# UAV_ARM.net
KiCad netlist of a schematic drawn in EAGLE
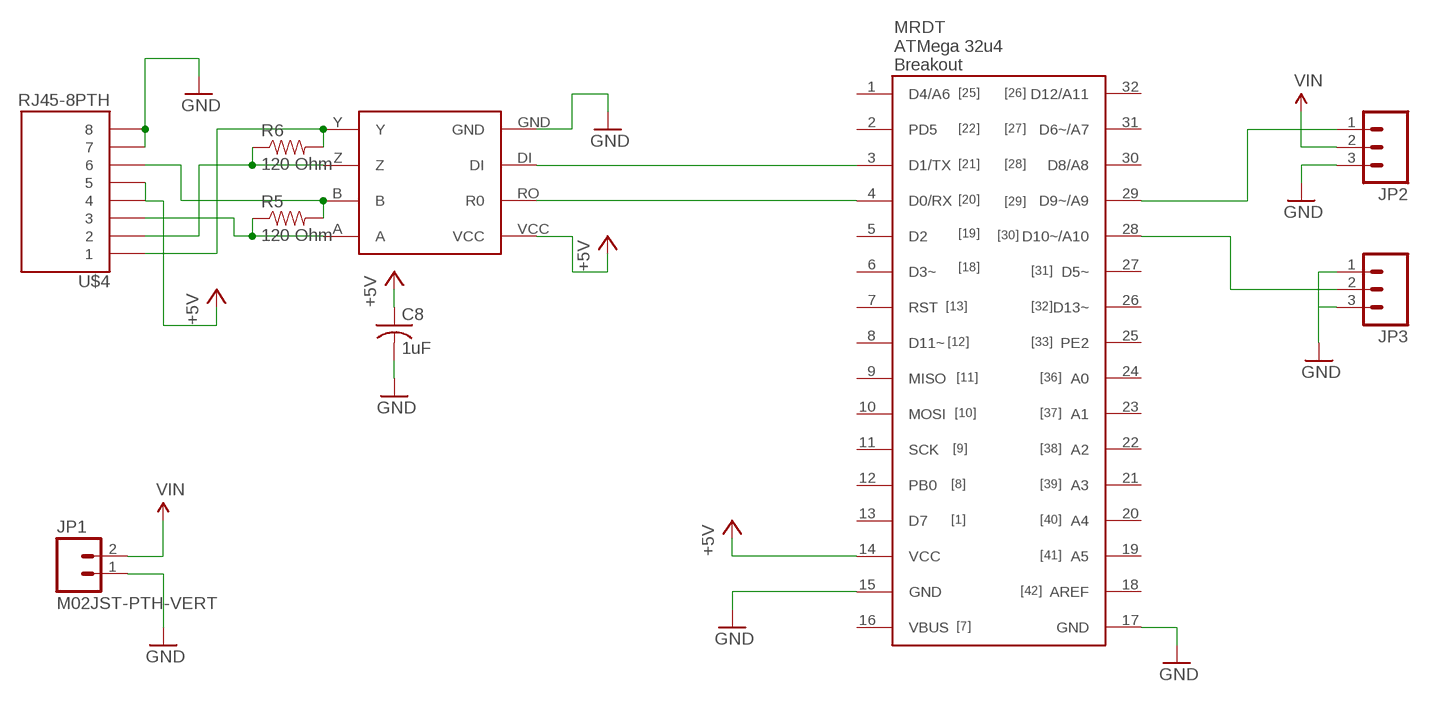
[diagram p0: schematic, sheet 1]

(export (version "E")
  (design (tool "Eeschema 10.0.6"))
  (components
    (comp (ref "C8")
      (value "1uF")
      (footprint "eagle-import:C1206")
      (libsource (lib "eagle-import") (part "C-USC1206"))
    )
    (comp (ref "JP1")
      (value "M02JST-PTH-VERT")
      (footprint "eagle-import:JST-2-PTH-VERT")
      (libsource (lib "eagle-import") (part "M02JST-PTH-VERT"))
    )
    (comp (ref "JP2")
      (value "M03JST-PTH")
      (footprint "eagle-import:JST-3-PTH")
      (libsource (lib "eagle-import") (part "M03JST-PTH"))
    )
    (comp (ref "JP3")
      (value "M03JST-PTH")
      (footprint "eagle-import:JST-3-PTH")
      (libsource (lib "eagle-import") (part "M03JST-PTH"))
    )
    (comp (ref "R5")
      (value "120 Ohm")
      (footprint "eagle-import:1206")
      (libsource (lib "eagle-import") (part "RESISTOR1206"))
    )
    (comp (ref "R6")
      (value "120 Ohm")
      (footprint "eagle-import:1206")
      (libsource (lib "eagle-import") (part "RESISTOR1206"))
    )
    (comp (ref "U$2")
      (value "32U4_BREAKOUT")
      (footprint "eagle-import:32U4_MCU_DIP")
      (libsource (lib "eagle-import") (part "32U4_BREAKOUT"))
    )
    (comp (ref "U$3")
      (value "MAX3077")
      (footprint "eagle-import:MAX3070E")
      (libsource (lib "eagle-import") (part "MAX3077"))
    )
    (comp (ref "U$4")
      (value "RJ45-8PTH")
      (footprint "eagle-import:RJ45-8")
      (libsource (lib "eagle-import") (part "RJ45-8PTH"))
    )
  )
  (nets
    (net (code "1") (name "+5V") (class "Default")
      (node (ref "C8") (pin "1") (pinfunction "1_1") (pintype "passive"))
      (node (ref "U$2") (pin "14") (pinfunction "VCC_14") (pintype "bidirectional"))
      (node (ref "U$3") (pin "VCC") (pinfunction "VCC_VCC") (pintype "bidirectional"))
      (node (ref "U$4") (pin "4") (pinfunction "4_4") (pintype "bidirectional"))
      (node (ref "U$4") (pin "5") (pinfunction "5_5") (pintype "bidirectional"))
    )
    (net (code "2") (name "GND") (class "Default")
      (node (ref "C8") (pin "2") (pinfunction "2_2") (pintype "passive"))
      (node (ref "JP1") (pin "1") (pinfunction "1_1") (pintype "passive"))
      (node (ref "JP2") (pin "3") (pinfunction "3_3") (pintype "passive"))
      (node (ref "JP3") (pin "1") (pinfunction "1_1") (pintype "passive"))
      (node (ref "JP3") (pin "3") (pinfunction "3_3") (pintype "passive"))
      (node (ref "U$2") (pin "15") (pinfunction "GND_15") (pintype "bidirectional"))
      (node (ref "U$2") (pin "17") (pinfunction "GND_17") (pintype "bidirectional"))
      (node (ref "U$3") (pin "GND") (pinfunction "GND_GND") (pintype "bidirectional"))
      (node (ref "U$4") (pin "7") (pinfunction "7_7") (pintype "bidirectional"))
      (node (ref "U$4") (pin "8") (pinfunction "8_8") (pintype "bidirectional"))
    )
    (net (code "3") (name "Net-(R5-Pad1)") (class "Default")
      (node (ref "R5") (pin "1") (pinfunction "1_1") (pintype "passive"))
      (node (ref "U$3") (pin "A") (pinfunction "A_A") (pintype "bidirectional"))
      (node (ref "U$4") (pin "3") (pinfunction "3_3") (pintype "bidirectional"))
    )
    (net (code "4") (name "Net-(R5-Pad2)") (class "Default")
      (node (ref "R5") (pin "2") (pinfunction "2_2") (pintype "passive"))
      (node (ref "U$3") (pin "B") (pinfunction "B_B") (pintype "bidirectional"))
      (node (ref "U$4") (pin "6") (pinfunction "6_6") (pintype "bidirectional"))
    )
    (net (code "5") (name "Net-(R6-Pad1)") (class "Default")
      (node (ref "R6") (pin "1") (pinfunction "1_1") (pintype "passive"))
      (node (ref "U$3") (pin "Z") (pinfunction "Z_Z") (pintype "bidirectional"))
      (node (ref "U$4") (pin "2") (pinfunction "2_2") (pintype "bidirectional"))
    )
    (net (code "6") (name "Net-(R6-Pad2)") (class "Default")
      (node (ref "R6") (pin "2") (pinfunction "2_2") (pintype "passive"))
      (node (ref "U$3") (pin "Y") (pinfunction "Y_Y") (pintype "bidirectional"))
      (node (ref "U$4") (pin "1") (pinfunction "1_1") (pintype "bidirectional"))
    )
    (net (code "7") (name "Net-(U$2-D0{slash}RX)") (class "Default")
      (node (ref "U$2") (pin "4") (pinfunction "D0/RX_4") (pintype "bidirectional"))
      (node (ref "U$3") (pin "RO") (pinfunction "R0_RO") (pintype "bidirectional"))
    )
    (net (code "8") (name "Net-(U$2-D1{slash}TX)") (class "Default")
      (node (ref "U$2") (pin "3") (pinfunction "D1/TX_3") (pintype "bidirectional"))
      (node (ref "U$3") (pin "DI") (pinfunction "DI_DI") (pintype "bidirectional"))
    )
    (net (code "9") (name "Net-(U$2-D9~{{slash}A9})") (class "Default")
      (node (ref "JP2") (pin "1") (pinfunction "1_1") (pintype "passive"))
      (node (ref "U$2") (pin "29") (pinfunction "D9~{/A9}_29") (pintype "bidirectional"))
    )
    (net (code "10") (name "Net-(U$2-D10~{{slash}A10})") (class "Default")
      (node (ref "JP3") (pin "2") (pinfunction "2_2") (pintype "passive"))
      (node (ref "U$2") (pin "28") (pinfunction "D10~{/A10}_28") (pintype "bidirectional"))
    )
    (net (code "11") (name "VIN") (class "Default")
      (node (ref "JP1") (pin "2") (pinfunction "2_2") (pintype "passive"))
      (node (ref "JP2") (pin "2") (pinfunction "2_2") (pintype "passive"))
    )
    (net (code "12") (name "unconnected-(U$2-A0-Pad24)") (class "Default")
      (node (ref "U$2") (pin "24") (pinfunction "A0_24") (pintype "bidirectional"))
    )
    (net (code "13") (name "unconnected-(U$2-A1-Pad23)") (class "Default")
      (node (ref "U$2") (pin "23") (pinfunction "A1_23") (pintype "bidirectional"))
    )
    (net (code "14") (name "unconnected-(U$2-A2-Pad22)") (class "Default")
      (node (ref "U$2") (pin "22") (pinfunction "A2_22") (pintype "bidirectional"))
    )
    (net (code "15") (name "unconnected-(U$2-A3-Pad21)") (class "Default")
      (node (ref "U$2") (pin "21") (pinfunction "A3_21") (pintype "bidirectional"))
    )
    (net (code "16") (name "unconnected-(U$2-A4-Pad20)") (class "Default")
      (node (ref "U$2") (pin "20") (pinfunction "A4_20") (pintype "bidirectional"))
    )
    (net (code "17") (name "unconnected-(U$2-A5-Pad19)") (class "Default")
      (node (ref "U$2") (pin "19") (pinfunction "A5_19") (pintype "bidirectional"))
    )
    (net (code "18") (name "unconnected-(U$2-AREF-Pad18)") (class "Default")
      (node (ref "U$2") (pin "18") (pinfunction "AREF_18") (pintype "bidirectional"))
    )
    (net (code "19") (name "unconnected-(U$2-D2-Pad5)") (class "Default")
      (node (ref "U$2") (pin "5") (pinfunction "D2_5") (pintype "bidirectional"))
    )
    (net (code "20") (name "unconnected-(U$2-D3~{}-Pad6)") (class "Default")
      (node (ref "U$2") (pin "6") (pinfunction "D3~{}_6") (pintype "bidirectional"))
    )
    (net (code "21") (name "unconnected-(U$2-D4{slash}A6-Pad1)") (class "Default")
      (node (ref "U$2") (pin "1") (pinfunction "D4/A6_1") (pintype "bidirectional"))
    )
    (net (code "22") (name "unconnected-(U$2-D5~{}-Pad27)") (class "Default")
      (node (ref "U$2") (pin "27") (pinfunction "D5~{}_27") (pintype "bidirectional"))
    )
    (net (code "23") (name "unconnected-(U$2-D6~{{slash}A7}-Pad31)") (class "Default")
      (node (ref "U$2") (pin "31") (pinfunction "D6~{/A7}_31") (pintype "bidirectional"))
    )
    (net (code "24") (name "unconnected-(U$2-D7-Pad13)") (class "Default")
      (node (ref "U$2") (pin "13") (pinfunction "D7_13") (pintype "bidirectional"))
    )
    (net (code "25") (name "unconnected-(U$2-D8{slash}A8-Pad30)") (class "Default")
      (node (ref "U$2") (pin "30") (pinfunction "D8/A8_30") (pintype "bidirectional"))
    )
    (net (code "26") (name "unconnected-(U$2-D11~{}-Pad8)") (class "Default")
      (node (ref "U$2") (pin "8") (pinfunction "D11~{}_8") (pintype "bidirectional"))
    )
    (net (code "27") (name "unconnected-(U$2-D12{slash}A11-Pad32)") (class "Default")
      (node (ref "U$2") (pin "32") (pinfunction "D12/A11_32") (pintype "bidirectional"))
    )
    (net (code "28") (name "unconnected-(U$2-D13~{}-Pad26)") (class "Default")
      (node (ref "U$2") (pin "26") (pinfunction "D13~{}_26") (pintype "bidirectional"))
    )
    (net (code "29") (name "unconnected-(U$2-MISO-Pad9)") (class "Default")
      (node (ref "U$2") (pin "9") (pinfunction "MISO_9") (pintype "bidirectional"))
    )
    (net (code "30") (name "unconnected-(U$2-MOSI-Pad10)") (class "Default")
      (node (ref "U$2") (pin "10") (pinfunction "MOSI_10") (pintype "bidirectional"))
    )
    (net (code "31") (name "unconnected-(U$2-PB0-Pad12)") (class "Default")
      (node (ref "U$2") (pin "12") (pinfunction "PB0_12") (pintype "bidirectional"))
    )
    (net (code "32") (name "unconnected-(U$2-PD5-Pad2)") (class "Default")
      (node (ref "U$2") (pin "2") (pinfunction "PD5_2") (pintype "bidirectional"))
    )
    (net (code "33") (name "unconnected-(U$2-PE2-Pad25)") (class "Default")
      (node (ref "U$2") (pin "25") (pinfunction "PE2_25") (pintype "bidirectional"))
    )
    (net (code "34") (name "unconnected-(U$2-RST-Pad7)") (class "Default")
      (node (ref "U$2") (pin "7") (pinfunction "RST_7") (pintype "bidirectional"))
    )
    (net (code "35") (name "unconnected-(U$2-SCK-Pad11)") (class "Default")
      (node (ref "U$2") (pin "11") (pinfunction "SCK_11") (pintype "bidirectional"))
    )
    (net (code "36") (name "unconnected-(U$2-VBUS-Pad16)") (class "Default")
      (node (ref "U$2") (pin "16") (pinfunction "VBUS_16") (pintype "bidirectional"))
    )
  )
)
